# CMPET456_Lab7_Schematic.net
KiCad netlist of a schematic drawn in EAGLE
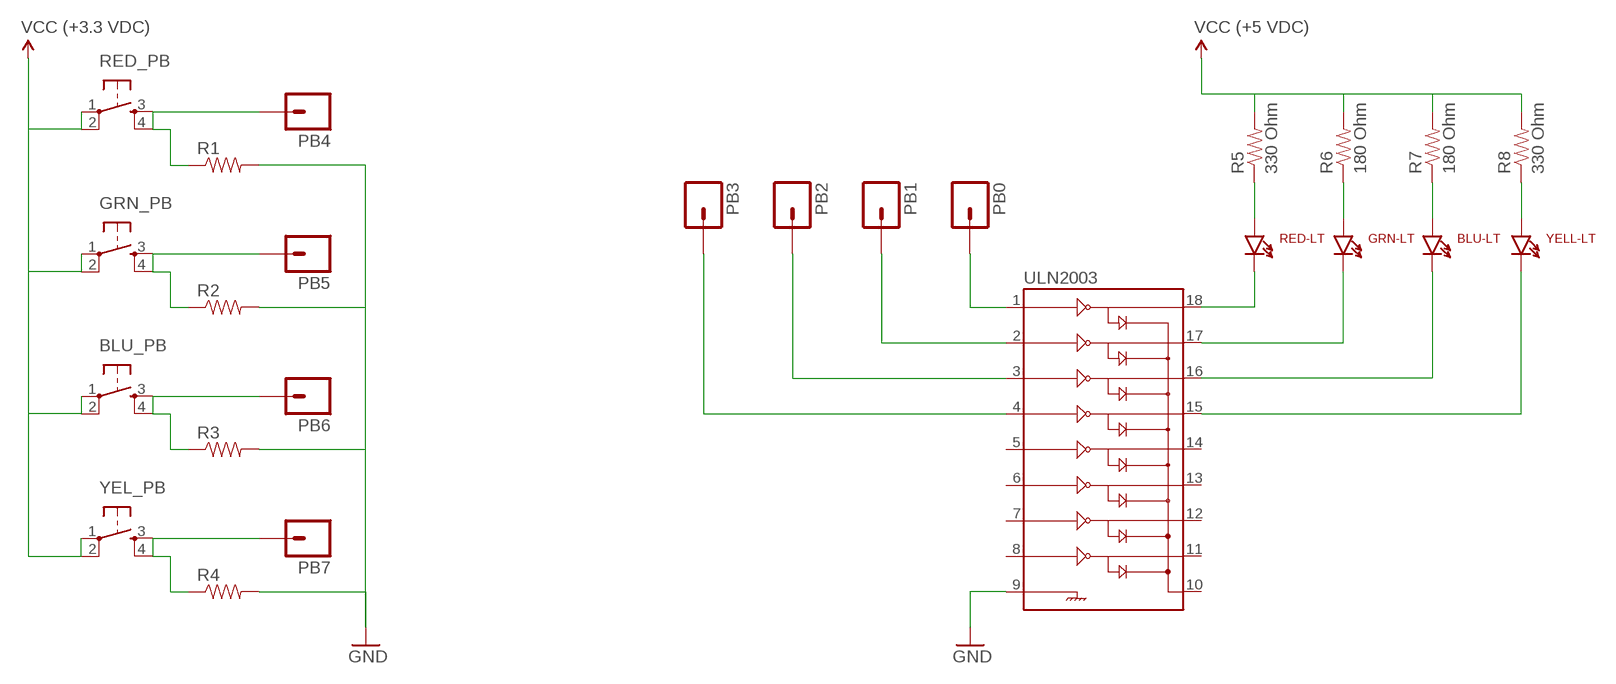
[diagram p0: schematic, sheet 1]

(export (version "E")
  (design (tool "Eeschema 10.0.6"))
  (components
    (comp (ref "BLU-LT")
      (value "LTE-302")
      (footprint "eagle-import:LTE-302")
      (libsource (lib "eagle-import") (part "LTE-302"))
    )
    (comp (ref "BLU_PB")
      (value "TAC_SWITCHPTH")
      (footprint "eagle-import:TACTILE-PTH")
      (libsource (lib "eagle-import") (part "TAC_SWITCHPTH"))
    )
    (comp (ref "GRN-LT")
      (value "LTE-302")
      (footprint "eagle-import:LTE-302")
      (libsource (lib "eagle-import") (part "LTE-302"))
    )
    (comp (ref "GRN_PB")
      (value "TAC_SWITCHPTH")
      (footprint "eagle-import:TACTILE-PTH")
      (libsource (lib "eagle-import") (part "TAC_SWITCHPTH"))
    )
    (comp (ref "PB0")
      (value "M01PTH")
      (footprint "eagle-import:1X01")
      (libsource (lib "eagle-import") (part "M01PTH"))
    )
    (comp (ref "PB1")
      (value "M01PTH")
      (footprint "eagle-import:1X01")
      (libsource (lib "eagle-import") (part "M01PTH"))
    )
    (comp (ref "PB2")
      (value "M01PTH")
      (footprint "eagle-import:1X01")
      (libsource (lib "eagle-import") (part "M01PTH"))
    )
    (comp (ref "PB3")
      (value "M01PTH")
      (footprint "eagle-import:1X01")
      (libsource (lib "eagle-import") (part "M01PTH"))
    )
    (comp (ref "PB4")
      (value "M01PTH")
      (footprint "eagle-import:1X01")
      (libsource (lib "eagle-import") (part "M01PTH"))
    )
    (comp (ref "PB5")
      (value "M01PTH")
      (footprint "eagle-import:1X01")
      (libsource (lib "eagle-import") (part "M01PTH"))
    )
    (comp (ref "PB6")
      (value "M01PTH")
      (footprint "eagle-import:1X01")
      (libsource (lib "eagle-import") (part "M01PTH"))
    )
    (comp (ref "PB7")
      (value "M01PTH")
      (footprint "eagle-import:1X01")
      (libsource (lib "eagle-import") (part "M01PTH"))
    )
    (comp (ref "R1")
      (value "RESISTOREZ")
      (footprint "eagle-import:AXIAL-0.3EZ")
      (libsource (lib "eagle-import") (part "RESISTOREZ"))
    )
    (comp (ref "R2")
      (value "RESISTOREZ")
      (footprint "eagle-import:AXIAL-0.3EZ")
      (libsource (lib "eagle-import") (part "RESISTOREZ"))
    )
    (comp (ref "R3")
      (value "RESISTOREZ")
      (footprint "eagle-import:AXIAL-0.3EZ")
      (libsource (lib "eagle-import") (part "RESISTOREZ"))
    )
    (comp (ref "R4")
      (value "RESISTOREZ")
      (footprint "eagle-import:AXIAL-0.3EZ")
      (libsource (lib "eagle-import") (part "RESISTOREZ"))
    )
    (comp (ref "R5")
      (value "330 Ohm")
      (footprint "eagle-import:AXIAL-0.3EZ")
      (libsource (lib "eagle-import") (part "RESISTOREZ"))
    )
    (comp (ref "R6")
      (value "180 Ohm")
      (footprint "eagle-import:AXIAL-0.3EZ")
      (libsource (lib "eagle-import") (part "RESISTOREZ"))
    )
    (comp (ref "R7")
      (value "180 Ohm")
      (footprint "eagle-import:AXIAL-0.3EZ")
      (libsource (lib "eagle-import") (part "RESISTOREZ"))
    )
    (comp (ref "R8")
      (value "330 Ohm")
      (footprint "eagle-import:AXIAL-0.3EZ")
      (libsource (lib "eagle-import") (part "RESISTOREZ"))
    )
    (comp (ref "RED-LT")
      (value "LTE-302")
      (footprint "eagle-import:LTE-302")
      (libsource (lib "eagle-import") (part "LTE-302"))
    )
    (comp (ref "RED_PB")
      (value "TAC_SWITCHPTH")
      (footprint "eagle-import:TACTILE-PTH")
      (libsource (lib "eagle-import") (part "TAC_SWITCHPTH"))
    )
    (comp (ref "ULN2003")
      (value "ULN2803DIP")
      (footprint "eagle-import:DIL18")
      (libsource (lib "eagle-import") (part "ULN2803DIP"))
    )
    (comp (ref "YELL-LT")
      (value "LTE-302")
      (footprint "eagle-import:LTE-302")
      (libsource (lib "eagle-import") (part "LTE-302"))
    )
    (comp (ref "YEL_PB")
      (value "TAC_SWITCHPTH")
      (footprint "eagle-import:TACTILE-PTH")
      (libsource (lib "eagle-import") (part "TAC_SWITCHPTH"))
    )
  )
  (nets
    (net (code "1") (name "GND") (class "Default")
      (node (ref "R1") (pin "P$2") (pinfunction "2_P$2") (pintype "passive"))
      (node (ref "R2") (pin "P$2") (pinfunction "2_P$2") (pintype "passive"))
      (node (ref "R3") (pin "P$2") (pinfunction "2_P$2") (pintype "passive"))
      (node (ref "R4") (pin "P$2") (pinfunction "2_P$2") (pintype "passive"))
      (node (ref "ULN2003") (pin "9") (pinfunction "9_9") (pintype "bidirectional"))
    )
    (net (code "2") (name "Net-(BLU-LT-PadC)") (class "Default")
      (node (ref "BLU-LT") (pin "C") (pinfunction "C_C") (pintype "bidirectional"))
      (node (ref "ULN2003") (pin "16") (pinfunction "16_16") (pintype "bidirectional"))
    )
    (net (code "3") (name "Net-(GRN-LT-PadC)") (class "Default")
      (node (ref "GRN-LT") (pin "C") (pinfunction "C_C") (pintype "bidirectional"))
      (node (ref "ULN2003") (pin "17") (pinfunction "17_17") (pintype "bidirectional"))
    )
    (net (code "4") (name "Net-(PB0-Pad1)") (class "Default")
      (node (ref "PB0") (pin "1") (pinfunction "1_1") (pintype "passive"))
      (node (ref "ULN2003") (pin "1") (pinfunction "1_1") (pintype "bidirectional"))
    )
    (net (code "5") (name "Net-(PB1-Pad1)") (class "Default")
      (node (ref "PB1") (pin "1") (pinfunction "1_1") (pintype "passive"))
      (node (ref "ULN2003") (pin "2") (pinfunction "2_2") (pintype "bidirectional"))
    )
    (net (code "6") (name "Net-(PB2-Pad1)") (class "Default")
      (node (ref "PB2") (pin "1") (pinfunction "1_1") (pintype "passive"))
      (node (ref "ULN2003") (pin "3") (pinfunction "3_3") (pintype "bidirectional"))
    )
    (net (code "7") (name "Net-(PB3-Pad1)") (class "Default")
      (node (ref "PB3") (pin "1") (pinfunction "1_1") (pintype "passive"))
      (node (ref "ULN2003") (pin "4") (pinfunction "4_4") (pintype "bidirectional"))
    )
    (net (code "8") (name "Net-(R1-1)") (class "Default")
      (node (ref "PB4") (pin "1") (pinfunction "1_1") (pintype "passive"))
      (node (ref "R1") (pin "P$1") (pinfunction "1_P$1") (pintype "passive"))
      (node (ref "RED_PB") (pin "3") (pinfunction "3_3") (pintype "passive"))
      (node (ref "RED_PB") (pin "4") (pinfunction "4_4") (pintype "passive"))
    )
    (net (code "9") (name "Net-(R2-1)") (class "Default")
      (node (ref "GRN_PB") (pin "3") (pinfunction "3_3") (pintype "passive"))
      (node (ref "GRN_PB") (pin "4") (pinfunction "4_4") (pintype "passive"))
      (node (ref "PB5") (pin "1") (pinfunction "1_1") (pintype "passive"))
      (node (ref "R2") (pin "P$1") (pinfunction "1_P$1") (pintype "passive"))
    )
    (net (code "10") (name "Net-(R3-1)") (class "Default")
      (node (ref "BLU_PB") (pin "3") (pinfunction "3_3") (pintype "passive"))
      (node (ref "BLU_PB") (pin "4") (pinfunction "4_4") (pintype "passive"))
      (node (ref "PB6") (pin "1") (pinfunction "1_1") (pintype "passive"))
      (node (ref "R3") (pin "P$1") (pinfunction "1_P$1") (pintype "passive"))
    )
    (net (code "11") (name "Net-(R4-1)") (class "Default")
      (node (ref "PB7") (pin "1") (pinfunction "1_1") (pintype "passive"))
      (node (ref "R4") (pin "P$1") (pinfunction "1_P$1") (pintype "passive"))
      (node (ref "YEL_PB") (pin "3") (pinfunction "3_3") (pintype "passive"))
      (node (ref "YEL_PB") (pin "4") (pinfunction "4_4") (pintype "passive"))
    )
    (net (code "12") (name "Net-(R5-1)") (class "Default")
      (node (ref "R5") (pin "P$1") (pinfunction "1_P$1") (pintype "passive"))
      (node (ref "RED-LT") (pin "A") (pinfunction "A_A") (pintype "bidirectional"))
    )
    (net (code "13") (name "Net-(R6-1)") (class "Default")
      (node (ref "GRN-LT") (pin "A") (pinfunction "A_A") (pintype "bidirectional"))
      (node (ref "R6") (pin "P$1") (pinfunction "1_P$1") (pintype "passive"))
    )
    (net (code "14") (name "Net-(R7-1)") (class "Default")
      (node (ref "BLU-LT") (pin "A") (pinfunction "A_A") (pintype "bidirectional"))
      (node (ref "R7") (pin "P$1") (pinfunction "1_P$1") (pintype "passive"))
    )
    (net (code "15") (name "Net-(R8-1)") (class "Default")
      (node (ref "R8") (pin "P$1") (pinfunction "1_P$1") (pintype "passive"))
      (node (ref "YELL-LT") (pin "A") (pinfunction "A_A") (pintype "bidirectional"))
    )
    (net (code "16") (name "Net-(RED-LT-PadC)") (class "Default")
      (node (ref "RED-LT") (pin "C") (pinfunction "C_C") (pintype "bidirectional"))
      (node (ref "ULN2003") (pin "18") (pinfunction "18_18") (pintype "bidirectional"))
    )
    (net (code "17") (name "Net-(ULN2003-Pad15)") (class "Default")
      (node (ref "ULN2003") (pin "15") (pinfunction "15_15") (pintype "bidirectional"))
      (node (ref "YELL-LT") (pin "C") (pinfunction "C_C") (pintype "bidirectional"))
    )
    (net (code "18") (name "VCC (+3.3 VDC)") (class "Default")
      (node (ref "BLU_PB") (pin "1") (pinfunction "1_1") (pintype "passive"))
      (node (ref "BLU_PB") (pin "2") (pinfunction "2_2") (pintype "passive"))
      (node (ref "GRN_PB") (pin "1") (pinfunction "1_1") (pintype "passive"))
      (node (ref "GRN_PB") (pin "2") (pinfunction "2_2") (pintype "passive"))
      (node (ref "R5") (pin "P$2") (pinfunction "2_P$2") (pintype "passive"))
      (node (ref "R6") (pin "P$2") (pinfunction "2_P$2") (pintype "passive"))
      (node (ref "R7") (pin "P$2") (pinfunction "2_P$2") (pintype "passive"))
      (node (ref "R8") (pin "P$2") (pinfunction "2_P$2") (pintype "passive"))
      (node (ref "RED_PB") (pin "1") (pinfunction "1_1") (pintype "passive"))
      (node (ref "RED_PB") (pin "2") (pinfunction "2_2") (pintype "passive"))
      (node (ref "YEL_PB") (pin "1") (pinfunction "1_1") (pintype "passive"))
      (node (ref "YEL_PB") (pin "2") (pinfunction "2_2") (pintype "passive"))
    )
    (net (code "19") (name "unconnected-(ULN2003-Pad5)") (class "Default")
      (node (ref "ULN2003") (pin "5") (pinfunction "5_5") (pintype "bidirectional"))
    )
    (net (code "20") (name "unconnected-(ULN2003-Pad6)") (class "Default")
      (node (ref "ULN2003") (pin "6") (pinfunction "6_6") (pintype "bidirectional"))
    )
    (net (code "21") (name "unconnected-(ULN2003-Pad7)") (class "Default")
      (node (ref "ULN2003") (pin "7") (pinfunction "7_7") (pintype "bidirectional"))
    )
    (net (code "22") (name "unconnected-(ULN2003-Pad8)") (class "Default")
      (node (ref "ULN2003") (pin "8") (pinfunction "8_8") (pintype "bidirectional"))
    )
    (net (code "23") (name "unconnected-(ULN2003-Pad10)") (class "Default")
      (node (ref "ULN2003") (pin "10") (pinfunction "10_10") (pintype "bidirectional"))
    )
    (net (code "24") (name "unconnected-(ULN2003-Pad11)") (class "Default")
      (node (ref "ULN2003") (pin "11") (pinfunction "11_11") (pintype "bidirectional"))
    )
    (net (code "25") (name "unconnected-(ULN2003-Pad12)") (class "Default")
      (node (ref "ULN2003") (pin "12") (pinfunction "12_12") (pintype "bidirectional"))
    )
    (net (code "26") (name "unconnected-(ULN2003-Pad13)") (class "Default")
      (node (ref "ULN2003") (pin "13") (pinfunction "13_13") (pintype "bidirectional"))
    )
    (net (code "27") (name "unconnected-(ULN2003-Pad14)") (class "Default")
      (node (ref "ULN2003") (pin "14") (pinfunction "14_14") (pintype "bidirectional"))
    )
  )
)
